# 01_Power_USB.net
KiCad netlist of a schematic drawn in Altium Designer
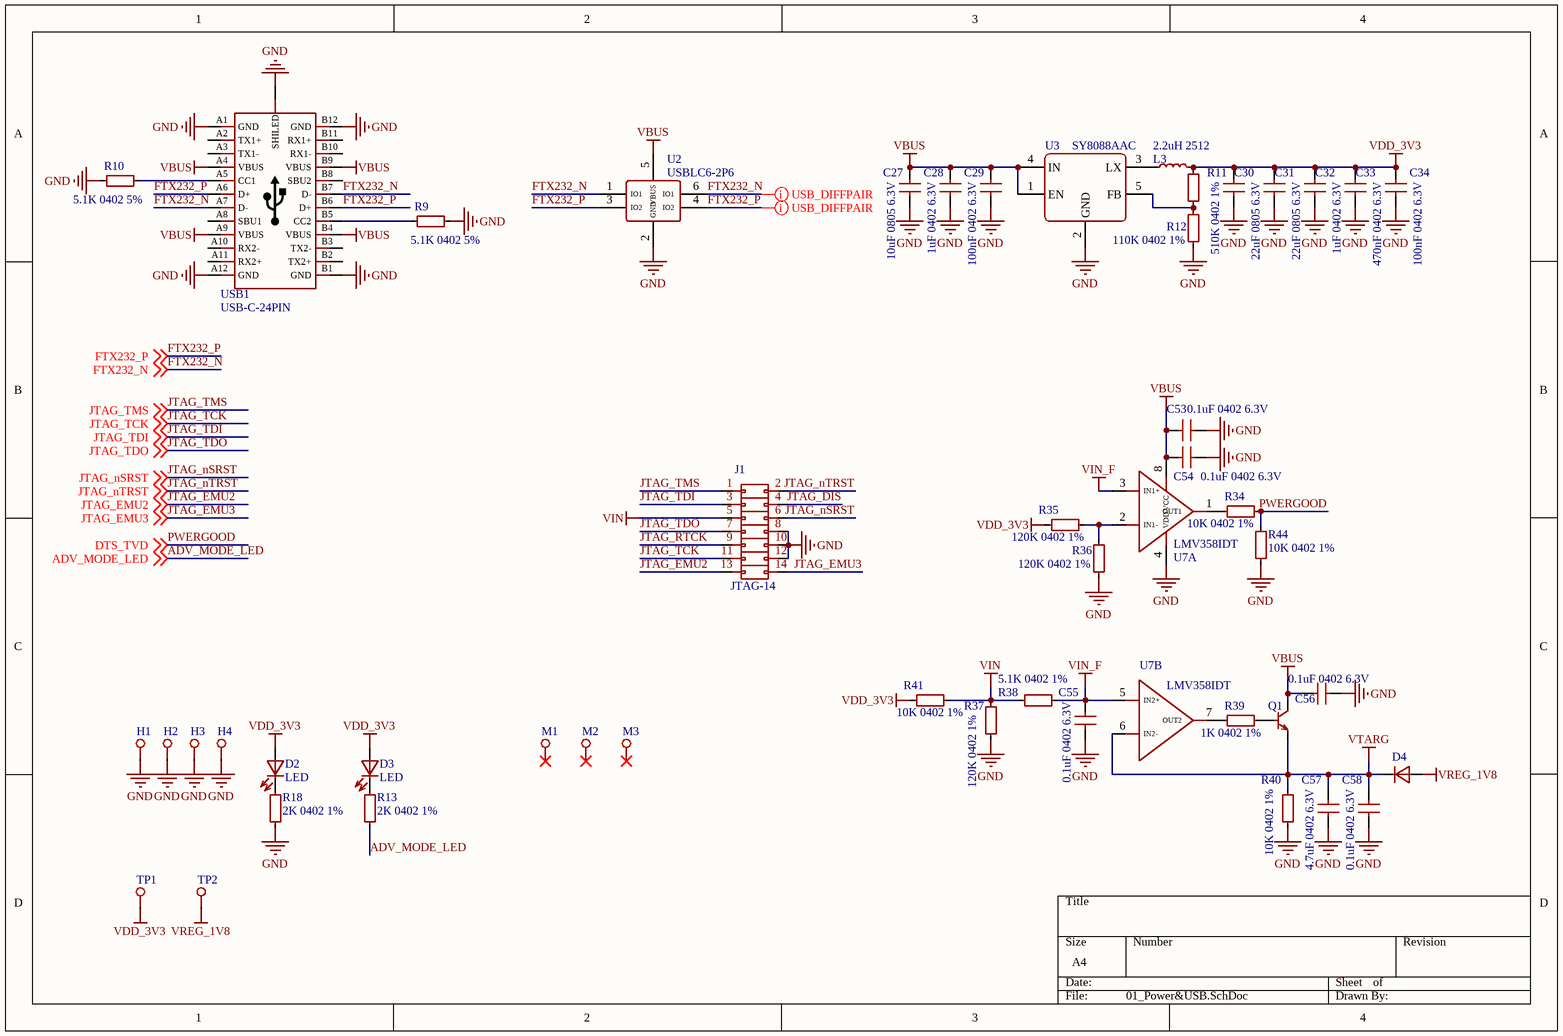
[diagram p0: 01_Power&USB.SchDoc]

(export (version "E")
  (design (tool "Eeschema 10.0.6"))
  (components
    (comp (ref "C27")
      (value "10uF 0805 6.3V")
      (footprint "C_0805_2012Metric")
      (description "Unpolarized capacitor")
      (libsource (lib "FPGA_VGA") (part "C"))
    )
    (comp (ref "C28")
      (value "1uF 0402 6.3V")
      (footprint "C_0402_1005Metric")
      (description "Unpolarized capacitor")
      (libsource (lib "FPGA_VGA") (part "C"))
    )
    (comp (ref "C29")
      (value "100nF 0402 6.3V")
      (footprint "C_0402_1005Metric")
      (description "Unpolarized capacitor")
      (libsource (lib "FPGA_VGA") (part "C"))
    )
    (comp (ref "C30")
      (value "22uF 0805 6.3V")
      (footprint "C_0805_2012Metric")
      (description "Unpolarized capacitor")
      (libsource (lib "FPGA_VGA") (part "C"))
    )
    (comp (ref "C31")
      (value "22uF 0805 6.3V")
      (footprint "C_0805_2012Metric")
      (description "Unpolarized capacitor")
      (libsource (lib "FPGA_VGA") (part "C"))
    )
    (comp (ref "C32")
      (value "1uF 0402 6.3V")
      (footprint "C_0402_1005Metric")
      (description "Unpolarized capacitor")
      (libsource (lib "FPGA_VGA") (part "C"))
    )
    (comp (ref "C33")
      (value "470nF 0402 6.3V")
      (footprint "C_0402_1005Metric")
      (description "Unpolarized capacitor")
      (libsource (lib "FPGA_VGA") (part "C"))
    )
    (comp (ref "C34")
      (value "100nF 0402 6.3V")
      (footprint "C_0402_1005Metric")
      (description "Unpolarized capacitor")
      (libsource (lib "FPGA_VGA") (part "C"))
    )
    (comp (ref "C53")
      (value "0.1uF 0402 6.3V")
      (footprint "C_0402_1005Metric")
      (description "Unpolarized capacitor")
      (libsource (lib "FPGA_VGA") (part "C"))
    )
    (comp (ref "C54")
      (value "0.1uF 0402 6.3V")
      (footprint "C_0402_1005Metric")
      (description "Unpolarized capacitor")
      (libsource (lib "FPGA_VGA") (part "C"))
    )
    (comp (ref "C55")
      (value "0.1uF 0402 6.3V")
      (footprint "C_0402_1005Metric")
      (description "Unpolarized capacitor")
      (libsource (lib "FPGA_VGA") (part "C"))
    )
    (comp (ref "C56")
      (value "0.1uF 0402 6.3V")
      (footprint "C_0402_1005Metric")
      (description "Unpolarized capacitor")
      (libsource (lib "FPGA_VGA") (part "C"))
    )
    (comp (ref "C57")
      (value "4.7uF 0402 6.3V")
      (footprint "C_0402_1005Metric")
      (description "Unpolarized capacitor")
      (libsource (lib "FPGA_VGA") (part "C"))
    )
    (comp (ref "C58")
      (value "0.1uF 0402 6.3V")
      (footprint "C_0402_1005Metric")
      (description "Unpolarized capacitor")
      (libsource (lib "FPGA_VGA") (part "C"))
    )
    (comp (ref "D2")
      (value "LED")
      (footprint "LED_0603_1608Metric")
      (description "Light emitting diode")
      (libsource (lib "FPGA_FTX232HL") (part "LED"))
    )
    (comp (ref "D3")
      (value "LED")
      (footprint "LED_0603_1608Metric")
      (description "Light emitting diode")
      (libsource (lib "FPGA_FTX232HL") (part "LED"))
    )
    (comp (ref "D4")
      (value "Diode")
      (footprint "SOD-523F_0P9X1P3_ONS")
      (description "Diode_AK")
      (libsource (lib "XDS100V3-anlogic") (part "Diode"))
    )
    (comp (ref "H1")
      (value "TestPoint")
      (footprint "M2-HOLE")
      (description "test point tp")
      (libsource (lib "FPGA_FTX232HL") (part "TestPoint"))
    )
    (comp (ref "H2")
      (value "TestPoint")
      (footprint "M2-HOLE")
      (description "test point tp")
      (libsource (lib "FPGA_FTX232HL") (part "TestPoint"))
    )
    (comp (ref "H3")
      (value "TestPoint")
      (footprint "M2-HOLE")
      (description "test point tp")
      (libsource (lib "FPGA_FTX232HL") (part "TestPoint"))
    )
    (comp (ref "H4")
      (value "TestPoint")
      (footprint "M2-HOLE")
      (description "test point tp")
      (libsource (lib "FPGA_FTX232HL") (part "TestPoint"))
    )
    (comp (ref "J1")
      (value "JTAG-14")
      (footprint "DC3_14P_2.54MM_V")
      (description "Generic connector, single row, 02x07,Odd Even")
      (libsource (lib "XDS100V3-anlogic") (part "Generic_Conn_02x07"))
    )
    (comp (ref "L3")
      (value "2.2uH 2512")
      (footprint "L_252012-TEMP")
      (description "Inductor")
      (libsource (lib "FPGA_FTX232HL") (part "L"))
    )
    (comp (ref "M1")
      (value "TestPoint")
      (footprint "Mark-1mm")
      (description "test point tp")
      (libsource (lib "FPGA_FTX232HL") (part "TestPoint"))
    )
    (comp (ref "M2")
      (value "TestPoint")
      (footprint "Mark-1mm")
      (description "test point tp")
      (libsource (lib "FPGA_FTX232HL") (part "TestPoint"))
    )
    (comp (ref "M3")
      (value "TestPoint")
      (footprint "Mark-1mm")
      (description "test point tp")
      (libsource (lib "FPGA_FTX232HL") (part "TestPoint"))
    )
    (comp (ref "Q1")
      (value "NPN-BEC")
      (footprint "NPN-BCE")
      (description "NPN transistor, base/collector/emitter for SOT23")
      (libsource (lib "XDS100V3-anlogic") (part "NPN-BEC"))
    )
    (comp (ref "R9")
      (value "5.1K 0402 5%")
      (footprint "R_0402_1005Metric")
      (description "Resistor")
      (libsource (lib "FPGA_VGA") (part "R"))
    )
    (comp (ref "R10")
      (value "5.1K 0402 5%")
      (footprint "R_0402_1005Metric")
      (description "Resistor")
      (libsource (lib "FPGA_VGA") (part "R"))
    )
    (comp (ref "R11")
      (value "510K 0402 1%")
      (footprint "R_0402_1005Metric")
      (description "Resistor")
      (libsource (lib "FPGA_VGA") (part "R"))
    )
    (comp (ref "R12")
      (value "110K 0402 1%")
      (footprint "R_0402_1005Metric")
      (description "Resistor")
      (libsource (lib "FPGA_VGA") (part "R"))
    )
    (comp (ref "R13")
      (value "2K 0402 1%")
      (footprint "R_0402_1005Metric")
      (description "Resistor")
      (libsource (lib "FPGA_VGA") (part "R"))
    )
    (comp (ref "R18")
      (value "2K 0402 1%")
      (footprint "R_0402_1005Metric")
      (description "Resistor")
      (libsource (lib "FPGA_VGA") (part "R"))
    )
    (comp (ref "R34")
      (value "10K 0402 1%")
      (footprint "R_0402_1005Metric")
      (description "Resistor")
      (libsource (lib "FPGA_VGA") (part "R"))
    )
    (comp (ref "R35")
      (value "120K 0402 1%")
      (footprint "R_0402_1005Metric")
      (description "Resistor")
      (libsource (lib "FPGA_VGA") (part "R"))
    )
    (comp (ref "R36")
      (value "120K 0402 1%")
      (footprint "R_0402_1005Metric")
      (description "Resistor")
      (libsource (lib "FPGA_VGA") (part "R"))
    )
    (comp (ref "R37")
      (value "120K 0402 1%")
      (footprint "R_0402_1005Metric")
      (description "Resistor")
      (libsource (lib "FPGA_VGA") (part "R"))
    )
    (comp (ref "R38")
      (value "5.1K 0402 1%")
      (footprint "R_0402_1005Metric")
      (description "Resistor")
      (libsource (lib "FPGA_VGA") (part "R"))
    )
    (comp (ref "R39")
      (value "1K 0402 1%")
      (footprint "R_0402_1005Metric")
      (description "Resistor")
      (libsource (lib "FPGA_VGA") (part "R"))
    )
    (comp (ref "R40")
      (value "10K 0402 1%")
      (footprint "R_0402_1005Metric")
      (description "Resistor")
      (libsource (lib "FPGA_VGA") (part "R"))
    )
    (comp (ref "R41")
      (value "10K 0402 1%")
      (footprint "R_0402_1005Metric")
      (description "Resistor")
      (libsource (lib "FPGA_VGA") (part "R"))
    )
    (comp (ref "R44")
      (value "10K 0402 1%")
      (footprint "R_0402_1005Metric")
      (description "Resistor")
      (libsource (lib "FPGA_VGA") (part "R"))
    )
    (comp (ref "TP1")
      (value "TestPoint")
      (footprint "TP-60MIL")
      (description "test point tp")
      (libsource (lib "FPGA_FTX232HL") (part "TestPoint"))
    )
    (comp (ref "TP2")
      (value "TestPoint")
      (footprint "TP-60MIL")
      (description "test point tp")
      (libsource (lib "FPGA_FTX232HL") (part "TestPoint"))
    )
    (comp (ref "U2")
      (value "USBLC6-2P6")
      (footprint "USBLC6-2P6-SOT-563")
      (description "Low Capacitance 2-Line ESD Protection")
      (libsource (lib "FPGA_FTX232HL") (part "USBLC6-2P6"))
    )
    (comp (ref "U3")
      (value "SY8088AAC")
      (footprint "SY8088AAC")
      (description "High Efficiency 1.5MHz, 1A\r\nSynchronous Step Down Regulator")
      (libsource (lib "FPGA_FTX232HL") (part "SY8088AAC"))
    )
    (comp (ref "U7")
      (value "LMV358IDT")
      (footprint "LMV358IDT-SOP8")
      (description "Low cost, low power, input/output rail-to-rail operational amplifiers")
      (libsource (lib "XDS100V3-anlogic") (part "LMV358IDT"))
    )
    (comp (ref "USB1")
      (value "USB-C-24PIN")
      (footprint "TYPE-C-16P-N0-ME")
      (libsource (lib "FPGA_FTX232HL") (part "USB-C-24PIN"))
    )
  )
  (nets
    (net (code "1") (name "/JTAG_DIS") (class "Default")
      (node (ref "J1") (pin "4") (pinfunction "4_4") (pintype "passive"))
    )
    (net (code "2") (name "/JTAG_RTCK") (class "Default")
      (node (ref "J1") (pin "9") (pinfunction "9_9") (pintype "passive"))
    )
    (net (code "3") (name "ADV_MODE_LED") (class "Default")
      (node (ref "R13") (pin "2") (pinfunction "2_2") (pintype "passive"))
    )
    (net (code "4") (name "DTS_TVD") (class "Default")
      (node (ref "R34") (pin "1") (pinfunction "1_1") (pintype "passive"))
      (node (ref "R44") (pin "1") (pinfunction "1_1") (pintype "passive"))
    )
    (net (code "5") (name "FTX232_N") (class "Default")
      (node (ref "U2") (pin "1") (pinfunction "IO1_1") (pintype "passive"))
      (node (ref "U2") (pin "6") (pinfunction "IO1_6") (pintype "passive"))
      (node (ref "USB1") (pin "A7") (pinfunction "D-_A7") (pintype "passive"))
      (node (ref "USB1") (pin "B7") (pinfunction "D-_B7") (pintype "passive"))
    )
    (net (code "6") (name "FTX232_P") (class "Default")
      (node (ref "U2") (pin "3") (pinfunction "IO2_3") (pintype "passive"))
      (node (ref "U2") (pin "4") (pinfunction "IO2_4") (pintype "passive"))
      (node (ref "USB1") (pin "A6") (pinfunction "D+_A6") (pintype "passive"))
      (node (ref "USB1") (pin "B6") (pinfunction "D+_B6") (pintype "passive"))
    )
    (net (code "7") (name "GND") (class "Default")
      (node (ref "C27") (pin "1") (pinfunction "1_1") (pintype "passive"))
      (node (ref "C28") (pin "1") (pinfunction "1_1") (pintype "passive"))
      (node (ref "C29") (pin "1") (pinfunction "1_1") (pintype "passive"))
      (node (ref "C30") (pin "1") (pinfunction "1_1") (pintype "passive"))
      (node (ref "C31") (pin "1") (pinfunction "1_1") (pintype "passive"))
      (node (ref "C32") (pin "1") (pinfunction "1_1") (pintype "passive"))
      (node (ref "C33") (pin "1") (pinfunction "1_1") (pintype "passive"))
      (node (ref "C34") (pin "1") (pinfunction "1_1") (pintype "passive"))
      (node (ref "C53") (pin "2") (pinfunction "2_2") (pintype "passive"))
      (node (ref "C54") (pin "2") (pinfunction "2_2") (pintype "passive"))
      (node (ref "C55") (pin "2") (pinfunction "2_2") (pintype "passive"))
      (node (ref "C56") (pin "2") (pinfunction "2_2") (pintype "passive"))
      (node (ref "C57") (pin "1") (pinfunction "1_1") (pintype "passive"))
      (node (ref "C58") (pin "1") (pinfunction "1_1") (pintype "passive"))
      (node (ref "H1") (pin "1") (pinfunction "1_1") (pintype "passive"))
      (node (ref "H2") (pin "1") (pinfunction "1_1") (pintype "passive"))
      (node (ref "H3") (pin "1") (pinfunction "1_1") (pintype "passive"))
      (node (ref "H4") (pin "1") (pinfunction "1_1") (pintype "passive"))
      (node (ref "J1") (pin "10") (pinfunction "10_10") (pintype "passive"))
      (node (ref "J1") (pin "12") (pinfunction "12_12") (pintype "passive"))
      (node (ref "J1") (pin "8") (pinfunction "8_8") (pintype "passive"))
      (node (ref "R10") (pin "1") (pinfunction "1_1") (pintype "passive"))
      (node (ref "R12") (pin "1") (pinfunction "1_1") (pintype "passive"))
      (node (ref "R18") (pin "2") (pinfunction "2_2") (pintype "passive"))
      (node (ref "R36") (pin "2") (pinfunction "2_2") (pintype "passive"))
      (node (ref "R37") (pin "2") (pinfunction "2_2") (pintype "passive"))
      (node (ref "R40") (pin "1") (pinfunction "1_1") (pintype "passive"))
      (node (ref "R44") (pin "2") (pinfunction "2_2") (pintype "passive"))
      (node (ref "R9") (pin "2") (pinfunction "2_2") (pintype "passive"))
      (node (ref "U2") (pin "2") (pinfunction "GND_2") (pintype "passive"))
      (node (ref "U3") (pin "2") (pinfunction "GND_2") (pintype "passive"))
      (node (ref "U7") (pin "4") (pinfunction "VDD_4") (pintype "passive"))
      (node (ref "USB1") (pin "A1") (pinfunction "GND_A1") (pintype "passive"))
      (node (ref "USB1") (pin "A12") (pinfunction "GND_A12") (pintype "passive"))
      (node (ref "USB1") (pin "B1") (pinfunction "GND_B1") (pintype "passive"))
      (node (ref "USB1") (pin "B12") (pinfunction "GND_B12") (pintype "passive"))
      (node (ref "USB1") (pin "SHILED") (pinfunction "SHILED_SHILED") (pintype "passive"))
    )
    (net (code "8") (name "JTAG_EMU2") (class "Default")
      (node (ref "J1") (pin "13") (pinfunction "13_13") (pintype "passive"))
    )
    (net (code "9") (name "JTAG_EMU3") (class "Default")
      (node (ref "J1") (pin "14") (pinfunction "14_14") (pintype "passive"))
    )
    (net (code "10") (name "JTAG_TCK") (class "Default")
      (node (ref "J1") (pin "11") (pinfunction "11_11") (pintype "passive"))
    )
    (net (code "11") (name "JTAG_TDI") (class "Default")
      (node (ref "J1") (pin "3") (pinfunction "3_3") (pintype "passive"))
    )
    (net (code "12") (name "JTAG_TDO") (class "Default")
      (node (ref "J1") (pin "7") (pinfunction "7_7") (pintype "passive"))
    )
    (net (code "13") (name "JTAG_TMS") (class "Default")
      (node (ref "J1") (pin "1") (pinfunction "1_1") (pintype "passive"))
    )
    (net (code "14") (name "JTAG_nSRST") (class "Default")
      (node (ref "J1") (pin "6") (pinfunction "6_6") (pintype "passive"))
    )
    (net (code "15") (name "JTAG_nTRST") (class "Default")
      (node (ref "J1") (pin "2") (pinfunction "2_2") (pintype "passive"))
    )
    (net (code "16") (name "Net-(D2-Pad2)") (class "Default")
      (node (ref "D2") (pin "2") (pinfunction "2_2") (pintype "passive"))
      (node (ref "R18") (pin "1") (pinfunction "1_1") (pintype "passive"))
    )
    (net (code "17") (name "Net-(D3-Pad2)") (class "Default")
      (node (ref "D3") (pin "2") (pinfunction "2_2") (pintype "passive"))
      (node (ref "R13") (pin "1") (pinfunction "1_1") (pintype "passive"))
    )
    (net (code "18") (name "Net-(Q1-B)") (class "Default")
      (node (ref "Q1") (pin "1") (pinfunction "B_1") (pintype "passive"))
      (node (ref "R39") (pin "2") (pinfunction "2_2") (pintype "passive"))
    )
    (net (code "19") (name "Net-(U3-FB)") (class "Default")
      (node (ref "R11") (pin "1") (pinfunction "1_1") (pintype "passive"))
      (node (ref "R12") (pin "2") (pinfunction "2_2") (pintype "passive"))
      (node (ref "U3") (pin "5") (pinfunction "FB_5") (pintype "passive"))
    )
    (net (code "20") (name "Net-(U3-LX)") (class "Default")
      (node (ref "L3") (pin "1") (pinfunction "1_1") (pintype "passive"))
      (node (ref "U3") (pin "3") (pinfunction "LX_3") (pintype "passive"))
    )
    (net (code "21") (name "Net-(U7A-IN1-)") (class "Default")
      (node (ref "R35") (pin "1") (pinfunction "1_1") (pintype "passive"))
      (node (ref "R36") (pin "1") (pinfunction "1_1") (pintype "passive"))
      (node (ref "U7") (pin "2") (pinfunction "IN1-_2") (pintype "passive"))
    )
    (net (code "22") (name "Net-(U7A-OUT1)") (class "Default")
      (node (ref "R34") (pin "2") (pinfunction "2_2") (pintype "passive"))
      (node (ref "U7") (pin "1") (pinfunction "OUT1_1") (pintype "passive"))
    )
    (net (code "23") (name "Net-(U7B-OUT2)") (class "Default")
      (node (ref "R39") (pin "1") (pinfunction "1_1") (pintype "passive"))
      (node (ref "U7") (pin "7") (pinfunction "OUT2_7") (pintype "passive"))
    )
    (net (code "24") (name "Net-(USB1-CC1)") (class "Default")
      (node (ref "R10") (pin "2") (pinfunction "2_2") (pintype "passive"))
      (node (ref "USB1") (pin "A5") (pinfunction "CC1_A5") (pintype "passive"))
    )
    (net (code "25") (name "Net-(USB1-CC2)") (class "Default")
      (node (ref "R9") (pin "1") (pinfunction "1_1") (pintype "passive"))
      (node (ref "USB1") (pin "B5") (pinfunction "CC2_B5") (pintype "passive"))
    )
    (net (code "26") (name "VBUS") (class "Default")
      (node (ref "C27") (pin "2") (pinfunction "2_2") (pintype "passive"))
      (node (ref "C28") (pin "2") (pinfunction "2_2") (pintype "passive"))
      (node (ref "C29") (pin "2") (pinfunction "2_2") (pintype "passive"))
      (node (ref "C53") (pin "1") (pinfunction "1_1") (pintype "passive"))
      (node (ref "C54") (pin "1") (pinfunction "1_1") (pintype "passive"))
      (node (ref "C56") (pin "1") (pinfunction "1_1") (pintype "passive"))
      (node (ref "Q1") (pin "3") (pinfunction "C_3") (pintype "passive"))
      (node (ref "U2") (pin "5") (pinfunction "VBUS_5") (pintype "passive"))
      (node (ref "U3") (pin "1") (pinfunction "EN_1") (pintype "passive"))
      (node (ref "U3") (pin "4") (pinfunction "IN_4") (pintype "passive"))
      (node (ref "U7") (pin "8") (pinfunction "VCC_8") (pintype "passive"))
      (node (ref "USB1") (pin "A4") (pinfunction "VBUS_A4") (pintype "passive"))
      (node (ref "USB1") (pin "A9") (pinfunction "VBUS_A9") (pintype "passive"))
      (node (ref "USB1") (pin "B4") (pinfunction "VBUS_B4") (pintype "passive"))
      (node (ref "USB1") (pin "B9") (pinfunction "VBUS_B9") (pintype "passive"))
    )
    (net (code "27") (name "VDD_3V3") (class "Default")
      (node (ref "C30") (pin "2") (pinfunction "2_2") (pintype "passive"))
      (node (ref "C31") (pin "2") (pinfunction "2_2") (pintype "passive"))
      (node (ref "C32") (pin "2") (pinfunction "2_2") (pintype "passive"))
      (node (ref "C33") (pin "2") (pinfunction "2_2") (pintype "passive"))
      (node (ref "C34") (pin "2") (pinfunction "2_2") (pintype "passive"))
      (node (ref "D2") (pin "1") (pinfunction "1_1") (pintype "passive"))
      (node (ref "D3") (pin "1") (pinfunction "1_1") (pintype "passive"))
      (node (ref "L3") (pin "2") (pinfunction "2_2") (pintype "passive"))
      (node (ref "R11") (pin "2") (pinfunction "2_2") (pintype "passive"))
      (node (ref "R35") (pin "2") (pinfunction "2_2") (pintype "passive"))
      (node (ref "R41") (pin "2") (pinfunction "2_2") (pintype "passive"))
      (node (ref "TP1") (pin "1") (pinfunction "1_1") (pintype "passive"))
    )
    (net (code "28") (name "VIN") (class "Default")
      (node (ref "J1") (pin "5") (pinfunction "5_5") (pintype "passive"))
      (node (ref "R37") (pin "1") (pinfunction "1_1") (pintype "passive"))
      (node (ref "R38") (pin "1") (pinfunction "1_1") (pintype "passive"))
      (node (ref "R41") (pin "1") (pinfunction "1_1") (pintype "passive"))
    )
    (net (code "29") (name "VIN_F") (class "Default")
      (node (ref "C55") (pin "1") (pinfunction "1_1") (pintype "passive"))
      (node (ref "R38") (pin "2") (pinfunction "2_2") (pintype "passive"))
      (node (ref "U7") (pin "3") (pinfunction "IN1+_3") (pintype "passive"))
      (node (ref "U7") (pin "5") (pinfunction "IN2+_5") (pintype "passive"))
    )
    (net (code "30") (name "VREG_1V8") (class "Default")
      (node (ref "D4") (pin "1") (pinfunction "1_1") (pintype "passive"))
      (node (ref "TP2") (pin "1") (pinfunction "1_1") (pintype "passive"))
    )
    (net (code "31") (name "VTARG") (class "Default")
      (node (ref "C57") (pin "2") (pinfunction "2_2") (pintype "passive"))
      (node (ref "C58") (pin "2") (pinfunction "2_2") (pintype "passive"))
      (node (ref "D4") (pin "2") (pinfunction "2_2") (pintype "passive"))
      (node (ref "Q1") (pin "2") (pinfunction "E_2") (pintype "passive"))
      (node (ref "R40") (pin "2") (pinfunction "2_2") (pintype "passive"))
      (node (ref "U7") (pin "6") (pinfunction "IN2-_6") (pintype "passive"))
    )
    (net (code "32") (name "unconnected-(M1-Pad1)") (class "Default")
      (node (ref "M1") (pin "1") (pinfunction "1_1") (pintype "passive+no_connect"))
    )
    (net (code "33") (name "unconnected-(M2-Pad1)") (class "Default")
      (node (ref "M2") (pin "1") (pinfunction "1_1") (pintype "passive+no_connect"))
    )
    (net (code "34") (name "unconnected-(M3-Pad1)") (class "Default")
      (node (ref "M3") (pin "1") (pinfunction "1_1") (pintype "passive+no_connect"))
    )
    (net (code "35") (name "unconnected-(USB1-RX1+-PadB11)") (class "Default")
      (node (ref "USB1") (pin "B11") (pinfunction "RX1+_B11") (pintype "passive"))
    )
    (net (code "36") (name "unconnected-(USB1-RX1--PadB10)") (class "Default")
      (node (ref "USB1") (pin "B10") (pinfunction "RX1-_B10") (pintype "passive"))
    )
    (net (code "37") (name "unconnected-(USB1-RX2+-PadA11)") (class "Default")
      (node (ref "USB1") (pin "A11") (pinfunction "RX2+_A11") (pintype "passive"))
    )
    (net (code "38") (name "unconnected-(USB1-RX2--PadA10)") (class "Default")
      (node (ref "USB1") (pin "A10") (pinfunction "RX2-_A10") (pintype "passive"))
    )
    (net (code "39") (name "unconnected-(USB1-SBU1-PadA8)") (class "Default")
      (node (ref "USB1") (pin "A8") (pinfunction "SBU1_A8") (pintype "passive"))
    )
    (net (code "40") (name "unconnected-(USB1-SBU2-PadB8)") (class "Default")
      (node (ref "USB1") (pin "B8") (pinfunction "SBU2_B8") (pintype "passive"))
    )
    (net (code "41") (name "unconnected-(USB1-TX1+-PadA2)") (class "Default")
      (node (ref "USB1") (pin "A2") (pinfunction "TX1+_A2") (pintype "passive"))
    )
    (net (code "42") (name "unconnected-(USB1-TX1--PadA3)") (class "Default")
      (node (ref "USB1") (pin "A3") (pinfunction "TX1-_A3") (pintype "passive"))
    )
    (net (code "43") (name "unconnected-(USB1-TX2+-PadB2)") (class "Default")
      (node (ref "USB1") (pin "B2") (pinfunction "TX2+_B2") (pintype "passive"))
    )
    (net (code "44") (name "unconnected-(USB1-TX2--PadB3)") (class "Default")
      (node (ref "USB1") (pin "B3") (pinfunction "TX2-_B3") (pintype "passive"))
    )
  )
)
